# MISO_LSH.net
KiCad netlist of a schematic drawn in Altium Designer
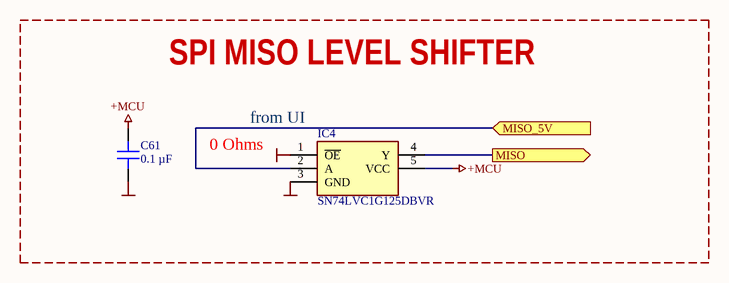
[diagram p0: MISO_LSH.SchDoc]

(export (version "E")
  (design (tool "Eeschema 10.0.6"))
  (components
    (comp (ref "C61")
      (value "0.1 µF")
      (footprint "CAP 0603_1608")
      (description "CAP CER 0.1UF 50V X7R 0603")
      (fields (field (name "PART NUMBER") "C0603C104K5RAC7411") (field (name "MANUFACTURER") "KEMET"))
      (libsource (lib "Celestial Altium Library - altium_library") (part "Capacitor"))
    )
    (comp (ref "IC4")
      (value "SN74LVC1G125DBVR")
      (footprint "ProtoStack_H750VBT:SOT95P280X145-5N")
      (description "Integrated Circuit")
      (fields (field (name "MOUSER PART NUMBER") "595-SN74LVC1G125DBVR"))
      (libsource (lib "ProtoStack_H750VBT") (part "SN74LVC1G125DBVR"))
    )
  )
  (nets
    (net (code "1") (name "+MCU") (class "Default")
      (node (ref "C61") (pin "1") (pinfunction "1_1") (pintype "passive"))
      (node (ref "IC4") (pin "5") (pinfunction "VCC_5") (pintype "passive"))
    )
    (net (code "2") (name "/MISO") (class "Default")
      (node (ref "IC4") (pin "4") (pinfunction "Y_4") (pintype "passive"))
    )
    (net (code "3") (name "/MISO_5V") (class "Default")
      (node (ref "IC4") (pin "2") (pinfunction "A_2") (pintype "passive"))
    )
    (net (code "4") (name "GND") (class "Default")
      (node (ref "C61") (pin "2") (pinfunction "2_2") (pintype "passive"))
      (node (ref "IC4") (pin "1") (pinfunction "~{OE}_1") (pintype "passive"))
      (node (ref "IC4") (pin "3") (pinfunction "GND_3") (pintype "passive"))
    )
  )
)
